# 10-Microcontroller-1.net
KiCad netlist of a schematic drawn in Altium Designer
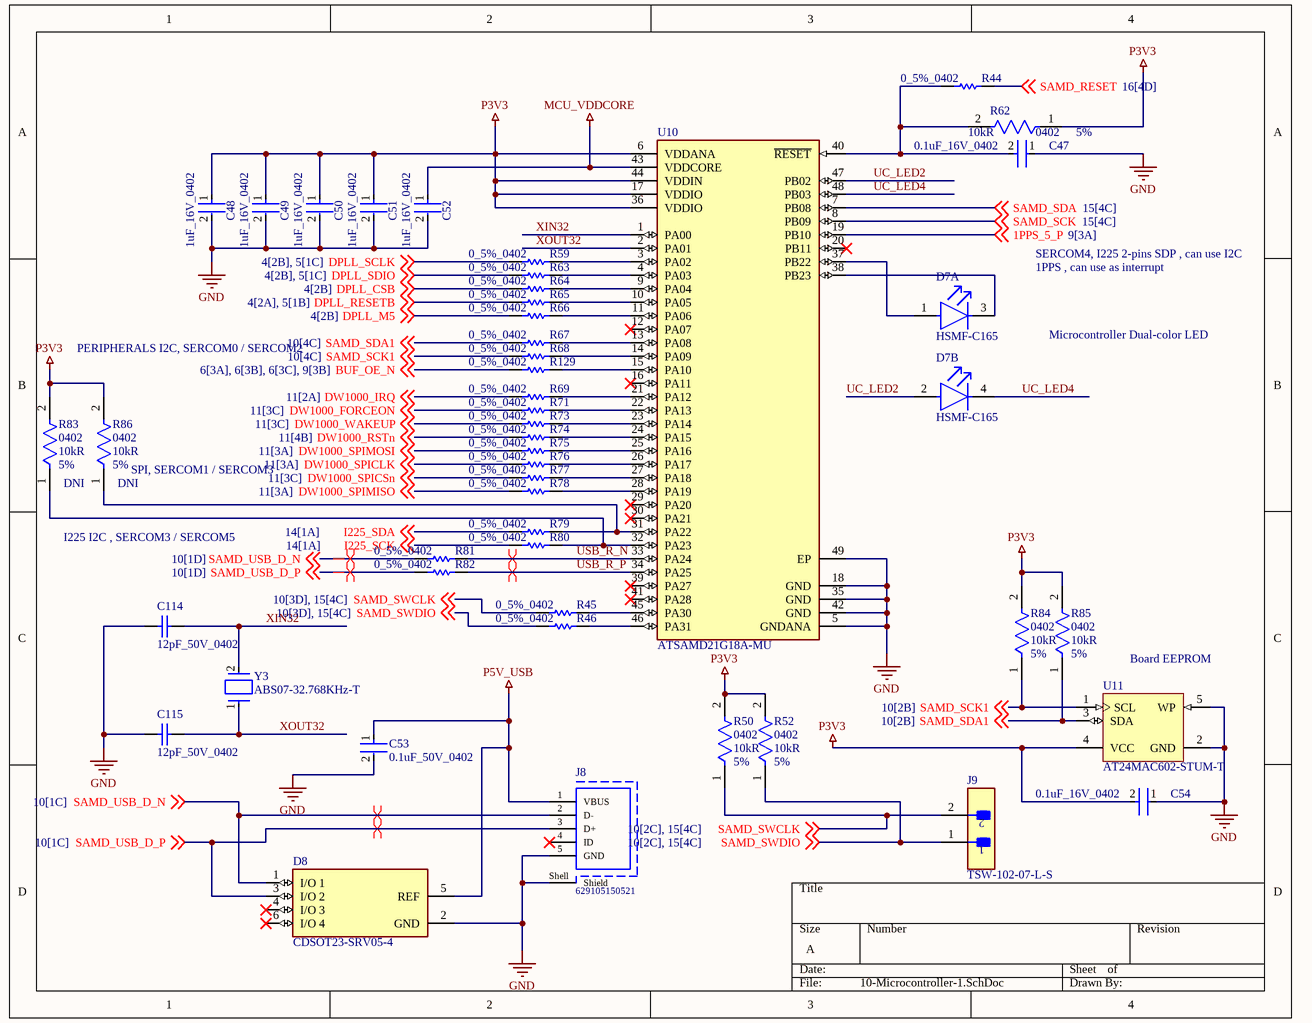
[diagram p0: 10-Microcontroller-1.SchDoc]

(export (version "E")
  (design (tool "Eeschema 10.0.6"))
  (components
    (comp (ref "C47")
      (value "0.1uF_16V_0402")
      (footprint "FP-GRM15-MFG")
      (description "CAP CER 0.1UF 16V X7R 0402")
      (fields (field (name "MANUFACTURER PART NUMBER") "GRM155R71C104KA88D") (field (name "TOLERANCE") "10%"))
      (libsource (lib "Altium Content Vault") (part "236180d848d6139a670b325ea6854c9"))
    )
    (comp (ref "C48")
      (value "1uF_16V_0402")
      (footprint "FP-0402-L_1_0_0_05-W_0_5-IPC_A")
      (description "None")
      (fields (field (name "TOLERANCE") "10%"))
      (libsource (lib "Altium Content Vault") (part "b4654b650e69147ec39a6b967a45e02"))
    )
    (comp (ref "C49")
      (value "1uF_16V_0402")
      (footprint "FP-0402-L_1_0_0_05-W_0_5-IPC_A")
      (description "None")
      (fields (field (name "TOLERANCE") "10%"))
      (libsource (lib "Altium Content Vault") (part "b4654b650e69147ec39a6b967a45e02"))
    )
    (comp (ref "C50")
      (value "1uF_16V_0402")
      (footprint "FP-0402-L_1_0_0_05-W_0_5-IPC_A")
      (description "None")
      (fields (field (name "TOLERANCE") "10%"))
      (libsource (lib "Altium Content Vault") (part "b4654b650e69147ec39a6b967a45e02"))
    )
    (comp (ref "C51")
      (value "1uF_16V_0402")
      (footprint "FP-0402-L_1_0_0_05-W_0_5-IPC_A")
      (description "None")
      (fields (field (name "TOLERANCE") "10%"))
      (libsource (lib "Altium Content Vault") (part "b4654b650e69147ec39a6b967a45e02"))
    )
    (comp (ref "C52")
      (value "1uF_16V_0402")
      (footprint "FP-0402-L_1_0_0_05-W_0_5-IPC_A")
      (description "None")
      (fields (field (name "TOLERANCE") "10%"))
      (libsource (lib "Altium Content Vault") (part "b4654b650e69147ec39a6b967a45e02"))
    )
    (comp (ref "C53")
      (value "0.1uF_50V_0402")
      (footprint "FP-C1005-050-0_05-IPC_C")
      (description "Multilayer Ceramic Capacitors 100nF ±10% 50V X7R SMD 0402")
      (fields (field (name "VOLTAGE") "50V") (field (name "TOLERANCE") "10%"))
      (libsource (lib "Altium Content Vault") (part "b4654b650e69147ec39a6b967a45e02"))
    )
    (comp (ref "C54")
      (value "0.1uF_16V_0402")
      (footprint "FP-GRM15-MFG")
      (description "CAP CER 0.1UF 16V X7R 0402")
      (fields (field (name "MANUFACTURER PART NUMBER") "GRM155R71C104KA88D") (field (name "TOLERANCE") "10%"))
      (libsource (lib "Altium Content Vault") (part "236180d848d6139a670b325ea6854c9"))
    )
    (comp (ref "C114")
      (value "12pF_50V_0402")
      (footprint "CAPC1005X55X25LL05T05")
      (description "Chip Capacitor, 12 pF, +/- 5%, 50 V, -55 to 125 degC, 0402 (1005 Metric), RoHS, Tape and Reel")
      (fields (field (name "MANUFACTURER") "Yageo") (field (name "TOLERANCE") "±5%"))
      (libsource (lib "Altium Content Vault") (part "CAP-NP-2"))
    )
    (comp (ref "C115")
      (value "12pF_50V_0402")
      (footprint "CAPC1005X55X25LL05T05")
      (description "Chip Capacitor, 12 pF, +/- 5%, 50 V, -55 to 125 degC, 0402 (1005 Metric), RoHS, Tape and Reel")
      (fields (field (name "MANUFACTURER") "Yageo") (field (name "TOLERANCE") "±5%"))
      (libsource (lib "Altium Content Vault") (part "CAP-NP-2"))
    )
    (comp (ref "D7")
      (value "HSMF-C165")
      (footprint "FP-HSMF-C165-MFG")
      (description "LED GREEN/RED DIFFUSED 0603 SMD")
      (libsource (lib "Altium Content Vault") (part "7c1fe340d8ce6b5db8c50b7ec3493de"))
    )
    (comp (ref "D8")
      (value "CDSOT23-SRV05-4")
      (footprint "FP-CDSOT23-SRV05-4-MFG")
      (description "TVS DIODE 5V 15V SOT23-6")
      (fields
        (field (name "OCTOPART") "https://octopart.com/cdsot23-srv05-4-bourns-1679449")
        (field (name "MANUFACTURER") "Bourns Inc.")
      )
      (libsource (lib "Altium Content Vault") (part "1f9d70c8dcd49be0b2fcd6c5f1da486"))
    )
    (comp (ref "J8")
      (value "629105150521")
      (footprint "629105150521")
      (description "Micro USB 2.0 Type B Receptacle WR-COM, Horizontal, SMT, with Pegs, High Current at Pin 1 & Pin 5")
      (fields (field (name "MANUFACTURER") "Wurth Elektronik") (field (name "PUBLISHER") "WurthElektronik"))
      (libsource (lib "Altium Content Vault") (part "WE-USB-5-1SHLD"))
    )
    (comp (ref "J9")
      (value "TSW-102-07-L-S")
      (footprint "FP-TSW-102-07-L-S-MFG")
      (description "CONN HEADER VERT 2POS 2.54MM")
      (libsource (lib "Altium Content Vault") (part "3bc925449376181038e59eaffc5286c"))
    )
    (comp (ref "R44")
      (value "0_5%_0402")
      (footprint "RESC1005X40X25LL10T10")
      (fields (field (name "MANUFACTURER") "KOA Speer") (field (name "PART NUMBER") "RK73Z1ETTP"))
      (libsource (lib "Altium Content Vault") (part "RES"))
    )
    (comp (ref "R45")
      (value "0_5%_0402")
      (footprint "RESC1005X40X25LL10T10")
      (fields (field (name "MANUFACTURER") "KOA Speer") (field (name "PART NUMBER") "RK73Z1ETTP"))
      (libsource (lib "Altium Content Vault") (part "RES"))
    )
    (comp (ref "R46")
      (value "0_5%_0402")
      (footprint "RESC1005X40X25LL10T10")
      (fields (field (name "MANUFACTURER") "KOA Speer") (field (name "PART NUMBER") "RK73Z1ETTP"))
      (libsource (lib "Altium Content Vault") (part "RES"))
    )
    (comp (ref "R50")
      (value "CRCW040210K0JNED")
      (footprint "FP-CRCW0402-e3-IPC_B")
      (description "RES Thick Film, 10kΩ, 5%, 0.063W, 200ppm/°C, 0402")
      (fields
        (field (name "CASE/PACKAGE") "0402")
        (field (name "RESISTANCE") "10kR")
        (field (name "TOLERANCE") "5%")
      )
      (libsource (lib "Altium Content Vault") (part "1029c3af85768c4190bb7ad29bc67b5"))
    )
    (comp (ref "R52")
      (value "CRCW040210K0JNED")
      (footprint "FP-CRCW0402-e3-IPC_B")
      (description "RES Thick Film, 10kΩ, 5%, 0.063W, 200ppm/°C, 0402")
      (fields
        (field (name "CASE/PACKAGE") "0402")
        (field (name "RESISTANCE") "10kR")
        (field (name "TOLERANCE") "5%")
      )
      (libsource (lib "Altium Content Vault") (part "1029c3af85768c4190bb7ad29bc67b5"))
    )
    (comp (ref "R59")
      (value "0_5%_0402")
      (footprint "RESC1005X40X25LL10T10")
      (fields (field (name "MANUFACTURER") "KOA Speer") (field (name "PART NUMBER") "RK73Z1ETTP"))
      (libsource (lib "Altium Content Vault") (part "RES"))
    )
    (comp (ref "R62")
      (value "CRCW040210K0JNED")
      (footprint "FP-CRCW0402-e3-IPC_B")
      (description "RES Thick Film, 10kΩ, 5%, 0.063W, 200ppm/°C, 0402")
      (fields
        (field (name "CASE/PACKAGE") "0402")
        (field (name "RESISTANCE") "10kR")
        (field (name "TOLERANCE") "5%")
      )
      (libsource (lib "Altium Content Vault") (part "1029c3af85768c4190bb7ad29bc67b5"))
    )
    (comp (ref "R63")
      (value "0_5%_0402")
      (footprint "RESC1005X40X25LL10T10")
      (fields (field (name "MANUFACTURER") "KOA Speer") (field (name "PART NUMBER") "RK73Z1ETTP"))
      (libsource (lib "Altium Content Vault") (part "RES"))
    )
    (comp (ref "R64")
      (value "0_5%_0402")
      (footprint "RESC1005X40X25LL10T10")
      (fields (field (name "MANUFACTURER") "KOA Speer") (field (name "PART NUMBER") "RK73Z1ETTP"))
      (libsource (lib "Altium Content Vault") (part "RES"))
    )
    (comp (ref "R65")
      (value "0_5%_0402")
      (footprint "RESC1005X40X25LL10T10")
      (fields (field (name "MANUFACTURER") "KOA Speer") (field (name "PART NUMBER") "RK73Z1ETTP"))
      (libsource (lib "Altium Content Vault") (part "RES"))
    )
    (comp (ref "R66")
      (value "0_5%_0402")
      (footprint "RESC1005X40X25LL10T10")
      (fields (field (name "MANUFACTURER") "KOA Speer") (field (name "PART NUMBER") "RK73Z1ETTP"))
      (libsource (lib "Altium Content Vault") (part "RES"))
    )
    (comp (ref "R67")
      (value "0_5%_0402")
      (footprint "RESC1005X40X25LL10T10")
      (fields (field (name "MANUFACTURER") "KOA Speer") (field (name "PART NUMBER") "RK73Z1ETTP"))
      (libsource (lib "Altium Content Vault") (part "RES"))
    )
    (comp (ref "R68")
      (value "0_5%_0402")
      (footprint "RESC1005X40X25LL10T10")
      (fields (field (name "MANUFACTURER") "KOA Speer") (field (name "PART NUMBER") "RK73Z1ETTP"))
      (libsource (lib "Altium Content Vault") (part "RES"))
    )
    (comp (ref "R69")
      (value "0_5%_0402")
      (footprint "RESC1005X40X25LL10T10")
      (fields (field (name "MANUFACTURER") "KOA Speer") (field (name "PART NUMBER") "RK73Z1ETTP"))
      (libsource (lib "Altium Content Vault") (part "RES"))
    )
    (comp (ref "R71")
      (value "0_5%_0402")
      (footprint "RESC1005X40X25LL10T10")
      (fields (field (name "MANUFACTURER") "KOA Speer") (field (name "PART NUMBER") "RK73Z1ETTP"))
      (libsource (lib "Altium Content Vault") (part "RES"))
    )
    (comp (ref "R73")
      (value "0_5%_0402")
      (footprint "RESC1005X40X25LL10T10")
      (fields (field (name "MANUFACTURER") "KOA Speer") (field (name "PART NUMBER") "RK73Z1ETTP"))
      (libsource (lib "Altium Content Vault") (part "RES"))
    )
    (comp (ref "R74")
      (value "0_5%_0402")
      (footprint "RESC1005X40X25LL10T10")
      (fields (field (name "MANUFACTURER") "KOA Speer") (field (name "PART NUMBER") "RK73Z1ETTP"))
      (libsource (lib "Altium Content Vault") (part "RES"))
    )
    (comp (ref "R75")
      (value "0_5%_0402")
      (footprint "RESC1005X40X25LL10T10")
      (fields (field (name "MANUFACTURER") "KOA Speer") (field (name "PART NUMBER") "RK73Z1ETTP"))
      (libsource (lib "Altium Content Vault") (part "RES"))
    )
    (comp (ref "R76")
      (value "0_5%_0402")
      (footprint "RESC1005X40X25LL10T10")
      (fields (field (name "MANUFACTURER") "KOA Speer") (field (name "PART NUMBER") "RK73Z1ETTP"))
      (libsource (lib "Altium Content Vault") (part "RES"))
    )
    (comp (ref "R77")
      (value "0_5%_0402")
      (footprint "RESC1005X40X25LL10T10")
      (fields (field (name "MANUFACTURER") "KOA Speer") (field (name "PART NUMBER") "RK73Z1ETTP"))
      (libsource (lib "Altium Content Vault") (part "RES"))
    )
    (comp (ref "R78")
      (value "0_5%_0402")
      (footprint "RESC1005X40X25LL10T10")
      (fields (field (name "MANUFACTURER") "KOA Speer") (field (name "PART NUMBER") "RK73Z1ETTP"))
      (libsource (lib "Altium Content Vault") (part "RES"))
    )
    (comp (ref "R79")
      (value "0_5%_0402")
      (footprint "RESC1005X40X25LL10T10")
      (fields (field (name "MANUFACTURER") "KOA Speer") (field (name "PART NUMBER") "RK73Z1ETTP"))
      (libsource (lib "Altium Content Vault") (part "RES"))
    )
    (comp (ref "R80")
      (value "0_5%_0402")
      (footprint "RESC1005X40X25LL10T10")
      (fields (field (name "MANUFACTURER") "KOA Speer") (field (name "PART NUMBER") "RK73Z1ETTP"))
      (libsource (lib "Altium Content Vault") (part "RES"))
    )
    (comp (ref "R81")
      (value "0_5%_0402")
      (footprint "RESC1005X40X25LL10T10")
      (fields (field (name "MANUFACTURER") "KOA Speer") (field (name "PART NUMBER") "RK73Z1ETTP"))
      (libsource (lib "Altium Content Vault") (part "RES"))
    )
    (comp (ref "R82")
      (value "0_5%_0402")
      (footprint "RESC1005X40X25LL10T10")
      (fields (field (name "MANUFACTURER") "KOA Speer") (field (name "PART NUMBER") "RK73Z1ETTP"))
      (libsource (lib "Altium Content Vault") (part "RES"))
    )
    (comp (ref "R83")
      (value "CRCW040210K0JNED")
      (footprint "FP-CRCW0402-e3-IPC_B")
      (description "RES Thick Film, 10kΩ, 5%, 0.063W, 200ppm/°C, 0402")
      (fields
        (field (name "CASE/PACKAGE") "0402")
        (field (name "RESISTANCE") "10kR")
        (field (name "TOLERANCE") "5%")
        (field (name "DNI") "DNI")
      )
      (libsource (lib "Altium Content Vault") (part "1029c3af85768c4190bb7ad29bc67b5"))
    )
    (comp (ref "R84")
      (value "CRCW040210K0JNED")
      (footprint "FP-CRCW0402-e3-IPC_B")
      (description "RES Thick Film, 10kΩ, 5%, 0.063W, 200ppm/°C, 0402")
      (fields
        (field (name "CASE/PACKAGE") "0402")
        (field (name "RESISTANCE") "10kR")
        (field (name "TOLERANCE") "5%")
      )
      (libsource (lib "Altium Content Vault") (part "1029c3af85768c4190bb7ad29bc67b5"))
    )
    (comp (ref "R85")
      (value "CRCW040210K0JNED")
      (footprint "FP-CRCW0402-e3-IPC_B")
      (description "RES Thick Film, 10kΩ, 5%, 0.063W, 200ppm/°C, 0402")
      (fields
        (field (name "CASE/PACKAGE") "0402")
        (field (name "RESISTANCE") "10kR")
        (field (name "TOLERANCE") "5%")
      )
      (libsource (lib "Altium Content Vault") (part "1029c3af85768c4190bb7ad29bc67b5"))
    )
    (comp (ref "R86")
      (value "CRCW040210K0JNED")
      (footprint "FP-CRCW0402-e3-IPC_B")
      (description "RES Thick Film, 10kΩ, 5%, 0.063W, 200ppm/°C, 0402")
      (fields
        (field (name "CASE/PACKAGE") "0402")
        (field (name "RESISTANCE") "10kR")
        (field (name "TOLERANCE") "5%")
        (field (name "DNI") "DNI")
      )
      (libsource (lib "Altium Content Vault") (part "1029c3af85768c4190bb7ad29bc67b5"))
    )
    (comp (ref "R129")
      (value "0_5%_0402")
      (footprint "RESC1005X40X25LL10T10")
      (fields (field (name "MANUFACTURER") "KOA Speer") (field (name "PART NUMBER") "RK73Z1ETTP"))
      (libsource (lib "Altium Content Vault") (part "RES"))
    )
    (comp (ref "U10")
      (value "ATSAMD21G18A-MU")
      (footprint "FP-C04-21493-MFG")
      (description "IC MCU 32BIT 256KB FLASH 48QFN")
      (libsource (lib "Altium Content Vault") (part "550eed7d4552ecbabbedec1abd3d356"))
    )
    (comp (ref "U11")
      (value "AT24MAC602-STUM-T")
      (footprint "ATML-5TS1_M")
      (fields (field (name "MANUFACTURER") "Atmel"))
      (libsource (lib "Altium Content Vault") (part "ATML-AT24CXXX-5TS1"))
    )
    (comp (ref "Y3")
      (value "ABS07-32.768KHz-T")
      (footprint "FP-ABS07-MFG")
      (description "CRYSTAL 32.7680KHZ 12.5PF SMD")
      (fields (field (name "TOLERANCE") "20ppm"))
      (libsource (lib "Altium Content Vault") (part "c23a69dc6c9e2f18f2079038eb95dd1"))
    )
  )
  (nets
    (net (code "1") (name "/UC_LED2") (class "Default")
      (node (ref "D7") (pin "2") (pinfunction "RED_A_2") (pintype "passive"))
      (node (ref "U10") (pin "47") (pinfunction "PB02_47") (pintype "bidirectional"))
    )
    (net (code "2") (name "/UC_LED4") (class "Default")
      (node (ref "D7") (pin "4") (pinfunction "RED_C_4") (pintype "passive"))
      (node (ref "U10") (pin "48") (pinfunction "PB03_48") (pintype "bidirectional"))
    )
    (net (code "3") (name "/USB_R_N") (class "Default")
      (node (ref "R81") (pin "2") (pinfunction "2_2") (pintype "passive"))
      (node (ref "U10") (pin "33") (pinfunction "PA24_33") (pintype "bidirectional"))
    )
    (net (code "4") (name "/USB_R_P") (class "Default")
      (node (ref "R82") (pin "2") (pinfunction "2_2") (pintype "passive"))
      (node (ref "U10") (pin "34") (pinfunction "PA25_34") (pintype "bidirectional"))
    )
    (net (code "5") (name "/XIN32") (class "Default")
      (node (ref "C114") (pin "1") (pinfunction "1_1") (pintype "passive"))
      (node (ref "U10") (pin "1") (pinfunction "PA00_1") (pintype "bidirectional"))
      (node (ref "Y3") (pin "2") (pinfunction "2_2") (pintype "passive"))
    )
    (net (code "6") (name "/XOUT32") (class "Default")
      (node (ref "C115") (pin "1") (pinfunction "1_1") (pintype "passive"))
      (node (ref "U10") (pin "2") (pinfunction "PA01_2") (pintype "bidirectional"))
      (node (ref "Y3") (pin "1") (pinfunction "1_1") (pintype "passive"))
    )
    (net (code "7") (name "1PPS_5_P") (class "Default")
      (node (ref "U10") (pin "19") (pinfunction "PB10_19") (pintype "bidirectional"))
    )
    (net (code "8") (name "BUF_OE_N") (class "Default")
      (node (ref "R129") (pin "1") (pinfunction "1_1") (pintype "passive"))
    )
    (net (code "9") (name "DPLL_CSB") (class "Default")
      (node (ref "R64") (pin "1") (pinfunction "1_1") (pintype "passive"))
    )
    (net (code "10") (name "DPLL_M5") (class "Default")
      (node (ref "R66") (pin "1") (pinfunction "1_1") (pintype "passive"))
    )
    (net (code "11") (name "DPLL_RESETB") (class "Default")
      (node (ref "R65") (pin "1") (pinfunction "1_1") (pintype "passive"))
    )
    (net (code "12") (name "DPLL_SCLK") (class "Default")
      (node (ref "R59") (pin "1") (pinfunction "1_1") (pintype "passive"))
    )
    (net (code "13") (name "DPLL_SDIO") (class "Default")
      (node (ref "R63") (pin "1") (pinfunction "1_1") (pintype "passive"))
    )
    (net (code "14") (name "DW1000_FORCEON") (class "Default")
      (node (ref "R71") (pin "1") (pinfunction "1_1") (pintype "passive"))
    )
    (net (code "15") (name "DW1000_IRQ") (class "Default")
      (node (ref "R69") (pin "1") (pinfunction "1_1") (pintype "passive"))
    )
    (net (code "16") (name "DW1000_RSTn") (class "Default")
      (node (ref "R74") (pin "1") (pinfunction "1_1") (pintype "passive"))
    )
    (net (code "17") (name "DW1000_SPICLK") (class "Default")
      (node (ref "R76") (pin "1") (pinfunction "1_1") (pintype "passive"))
    )
    (net (code "18") (name "DW1000_SPICSn") (class "Default")
      (node (ref "R77") (pin "1") (pinfunction "1_1") (pintype "passive"))
    )
    (net (code "19") (name "DW1000_SPIMISO") (class "Default")
      (node (ref "R78") (pin "1") (pinfunction "1_1") (pintype "passive"))
    )
    (net (code "20") (name "DW1000_SPIMOSI") (class "Default")
      (node (ref "R75") (pin "1") (pinfunction "1_1") (pintype "passive"))
    )
    (net (code "21") (name "DW1000_WAKEUP") (class "Default")
      (node (ref "R73") (pin "1") (pinfunction "1_1") (pintype "passive"))
    )
    (net (code "22") (name "GND") (class "Default")
      (node (ref "C114") (pin "2") (pinfunction "2_2") (pintype "passive"))
      (node (ref "C115") (pin "2") (pinfunction "2_2") (pintype "passive"))
      (node (ref "C47") (pin "1") (pinfunction "1_1") (pintype "passive"))
      (node (ref "C48") (pin "2") (pinfunction "2_2") (pintype "passive"))
      (node (ref "C49") (pin "2") (pinfunction "2_2") (pintype "passive"))
      (node (ref "C50") (pin "2") (pinfunction "2_2") (pintype "passive"))
      (node (ref "C51") (pin "2") (pinfunction "2_2") (pintype "passive"))
      (node (ref "C52") (pin "2") (pinfunction "2_2") (pintype "passive"))
      (node (ref "C53") (pin "2") (pinfunction "2_2") (pintype "passive"))
      (node (ref "C54") (pin "1") (pinfunction "1_1") (pintype "passive"))
      (node (ref "D8") (pin "2") (pinfunction "GND_2") (pintype "power_in"))
      (node (ref "J8") (pin "5") (pinfunction "GND_5") (pintype "passive"))
      (node (ref "J8") (pin "Shell") (pinfunction "Shield_Shell") (pintype "passive"))
      (node (ref "U10") (pin "18") (pinfunction "GND_18") (pintype "power_in"))
      (node (ref "U10") (pin "35") (pinfunction "GND_35") (pintype "power_in"))
      (node (ref "U10") (pin "42") (pinfunction "GND_42") (pintype "power_in"))
      (node (ref "U10") (pin "49") (pinfunction "EP_49") (pintype "power_in"))
      (node (ref "U10") (pin "5") (pinfunction "GNDANA_5") (pintype "power_in"))
      (node (ref "U11") (pin "2") (pinfunction "GND_2") (pintype "power_in"))
      (node (ref "U11") (pin "5") (pinfunction "WP_5") (pintype "input"))
    )
    (net (code "23") (name "I225_SCK") (class "Default")
      (node (ref "R80") (pin "1") (pinfunction "1_1") (pintype "passive"))
    )
    (net (code "24") (name "I225_SDA") (class "Default")
      (node (ref "R79") (pin "1") (pinfunction "1_1") (pintype "passive"))
    )
    (net (code "25") (name "MCU_VDDCORE") (class "Default")
      (node (ref "C52") (pin "1") (pinfunction "1_1") (pintype "passive"))
      (node (ref "U10") (pin "43") (pinfunction "VDDCORE_43") (pintype "power_in"))
    )
    (net (code "26") (name "Net-(D7A-GREEN_A)") (class "Default")
      (node (ref "D7") (pin "1") (pinfunction "GREEN_A_1") (pintype "passive"))
      (node (ref "U10") (pin "37") (pinfunction "PB22_37") (pintype "bidirectional"))
    )
    (net (code "27") (name "Net-(D7A-GREEN_C)") (class "Default")
      (node (ref "D7") (pin "3") (pinfunction "GREEN_C_3") (pintype "passive"))
      (node (ref "U10") (pin "38") (pinfunction "PB23_38") (pintype "bidirectional"))
    )
    (net (code "28") (name "Net-(U10-PA02)") (class "Default")
      (node (ref "R59") (pin "2") (pinfunction "2_2") (pintype "passive"))
      (node (ref "U10") (pin "3") (pinfunction "PA02_3") (pintype "bidirectional"))
    )
    (net (code "29") (name "Net-(U10-PA03)") (class "Default")
      (node (ref "R63") (pin "2") (pinfunction "2_2") (pintype "passive"))
      (node (ref "U10") (pin "4") (pinfunction "PA03_4") (pintype "bidirectional"))
    )
    (net (code "30") (name "Net-(U10-PA04)") (class "Default")
      (node (ref "R64") (pin "2") (pinfunction "2_2") (pintype "passive"))
      (node (ref "U10") (pin "9") (pinfunction "PA04_9") (pintype "bidirectional"))
    )
    (net (code "31") (name "Net-(U10-PA05)") (class "Default")
      (node (ref "R65") (pin "2") (pinfunction "2_2") (pintype "passive"))
      (node (ref "U10") (pin "10") (pinfunction "PA05_10") (pintype "bidirectional"))
    )
    (net (code "32") (name "Net-(U10-PA06)") (class "Default")
      (node (ref "R66") (pin "2") (pinfunction "2_2") (pintype "passive"))
      (node (ref "U10") (pin "11") (pinfunction "PA06_11") (pintype "bidirectional"))
    )
    (net (code "33") (name "Net-(U10-PA08)") (class "Default")
      (node (ref "R67") (pin "2") (pinfunction "2_2") (pintype "passive"))
      (node (ref "U10") (pin "13") (pinfunction "PA08_13") (pintype "bidirectional"))
    )
    (net (code "34") (name "Net-(U10-PA09)") (class "Default")
      (node (ref "R68") (pin "2") (pinfunction "2_2") (pintype "passive"))
      (node (ref "U10") (pin "14") (pinfunction "PA09_14") (pintype "bidirectional"))
    )
    (net (code "35") (name "Net-(U10-PA10)") (class "Default")
      (node (ref "R129") (pin "2") (pinfunction "2_2") (pintype "passive"))
      (node (ref "U10") (pin "15") (pinfunction "PA10_15") (pintype "bidirectional"))
    )
    (net (code "36") (name "Net-(U10-PA12)") (class "Default")
      (node (ref "R69") (pin "2") (pinfunction "2_2") (pintype "passive"))
      (node (ref "U10") (pin "21") (pinfunction "PA12_21") (pintype "bidirectional"))
    )
    (net (code "37") (name "Net-(U10-PA13)") (class "Default")
      (node (ref "R71") (pin "2") (pinfunction "2_2") (pintype "passive"))
      (node (ref "U10") (pin "22") (pinfunction "PA13_22") (pintype "bidirectional"))
    )
    (net (code "38") (name "Net-(U10-PA14)") (class "Default")
      (node (ref "R73") (pin "2") (pinfunction "2_2") (pintype "passive"))
      (node (ref "U10") (pin "23") (pinfunction "PA14_23") (pintype "bidirectional"))
    )
    (net (code "39") (name "Net-(U10-PA15)") (class "Default")
      (node (ref "R74") (pin "2") (pinfunction "2_2") (pintype "passive"))
      (node (ref "U10") (pin "24") (pinfunction "PA15_24") (pintype "bidirectional"))
    )
    (net (code "40") (name "Net-(U10-PA16)") (class "Default")
      (node (ref "R75") (pin "2") (pinfunction "2_2") (pintype "passive"))
      (node (ref "U10") (pin "25") (pinfunction "PA16_25") (pintype "bidirectional"))
    )
    (net (code "41") (name "Net-(U10-PA17)") (class "Default")
      (node (ref "R76") (pin "2") (pinfunction "2_2") (pintype "passive"))
      (node (ref "U10") (pin "26") (pinfunction "PA17_26") (pintype "bidirectional"))
    )
    (net (code "42") (name "Net-(U10-PA18)") (class "Default")
      (node (ref "R77") (pin "2") (pinfunction "2_2") (pintype "passive"))
      (node (ref "U10") (pin "27") (pinfunction "PA18_27") (pintype "bidirectional"))
    )
    (net (code "43") (name "Net-(U10-PA19)") (class "Default")
      (node (ref "R78") (pin "2") (pinfunction "2_2") (pintype "passive"))
      (node (ref "U10") (pin "28") (pinfunction "PA19_28") (pintype "bidirectional"))
    )
    (net (code "44") (name "Net-(U10-PA22)") (class "Default")
      (node (ref "R79") (pin "2") (pinfunction "2_2") (pintype "passive"))
      (node (ref "R86") (pin "1") (pinfunction "1_1") (pintype "passive"))
      (node (ref "U10") (pin "31") (pinfunction "PA22_31") (pintype "bidirectional"))
    )
    (net (code "45") (name "Net-(U10-PA23)") (class "Default")
      (node (ref "R80") (pin "2") (pinfunction "2_2") (pintype "passive"))
      (node (ref "R83") (pin "1") (pinfunction "1_1") (pintype "passive"))
      (node (ref "U10") (pin "32") (pinfunction "PA23_32") (pintype "bidirectional"))
    )
    (net (code "46") (name "Net-(U10-PA30)") (class "Default")
      (node (ref "R45") (pin "2") (pinfunction "2_2") (pintype "passive"))
      (node (ref "U10") (pin "45") (pinfunction "PA30_45") (pintype "bidirectional"))
    )
    (net (code "47") (name "Net-(U10-PA31)") (class "Default")
      (node (ref "R46") (pin "2") (pinfunction "2_2") (pintype "passive"))
      (node (ref "U10") (pin "46") (pinfunction "PA31_46") (pintype "bidirectional"))
    )
    (net (code "48") (name "Net-(U10-~{RESET})") (class "Default")
      (node (ref "C47") (pin "2") (pinfunction "2_2") (pintype "passive"))
      (node (ref "R44") (pin "1") (pinfunction "1_1") (pintype "passive"))
      (node (ref "R62") (pin "2") (pinfunction "2_2") (pintype "passive"))
      (node (ref "U10") (pin "40") (pinfunction "~{RESET}_40") (pintype "input"))
    )
    (net (code "49") (name "P3V3") (class "Default")
      (node (ref "C48") (pin "1") (pinfunction "1_1") (pintype "passive"))
      (node (ref "C49") (pin "1") (pinfunction "1_1") (pintype "passive"))
      (node (ref "C50") (pin "1") (pinfunction "1_1") (pintype "passive"))
      (node (ref "C51") (pin "1") (pinfunction "1_1") (pintype "passive"))
      (node (ref "C54") (pin "2") (pinfunction "2_2") (pintype "passive"))
      (node (ref "R50") (pin "2") (pinfunction "2_2") (pintype "passive"))
      (node (ref "R52") (pin "2") (pinfunction "2_2") (pintype "passive"))
      (node (ref "R62") (pin "1") (pinfunction "1_1") (pintype "passive"))
      (node (ref "R83") (pin "2") (pinfunction "2_2") (pintype "passive"))
      (node (ref "R84") (pin "2") (pinfunction "2_2") (pintype "passive"))
      (node (ref "R85") (pin "2") (pinfunction "2_2") (pintype "passive"))
      (node (ref "R86") (pin "2") (pinfunction "2_2") (pintype "passive"))
      (node (ref "U10") (pin "17") (pinfunction "VDDIO_17") (pintype "power_in"))
      (node (ref "U10") (pin "36") (pinfunction "VDDIO_36") (pintype "power_in"))
      (node (ref "U10") (pin "44") (pinfunction "VDDIN_44") (pintype "power_in"))
      (node (ref "U10") (pin "6") (pinfunction "VDDANA_6") (pintype "power_in"))
      (node (ref "U11") (pin "4") (pinfunction "VCC_4") (pintype "power_in"))
    )
    (net (code "50") (name "P5V_USB") (class "Default")
      (node (ref "C53") (pin "1") (pinfunction "1_1") (pintype "passive"))
      (node (ref "D8") (pin "5") (pinfunction "REF_5") (pintype "power_in"))
      (node (ref "J8") (pin "1") (pinfunction "VBUS_1") (pintype "passive"))
    )
    (net (code "51") (name "SAMD_RESET") (class "Default")
      (node (ref "R44") (pin "2") (pinfunction "2_2") (pintype "passive"))
    )
    (net (code "52") (name "SAMD_SCK") (class "Default")
      (node (ref "U10") (pin "8") (pinfunction "PB09_8") (pintype "bidirectional"))
    )
    (net (code "53") (name "SAMD_SCK1") (class "Default")
      (node (ref "R68") (pin "1") (pinfunction "1_1") (pintype "passive"))
      (node (ref "R84") (pin "1") (pinfunction "1_1") (pintype "passive"))
      (node (ref "U11") (pin "1") (pinfunction "SCL_1") (pintype "input"))
    )
    (net (code "54") (name "SAMD_SDA") (class "Default")
      (node (ref "U10") (pin "7") (pinfunction "PB08_7") (pintype "bidirectional"))
    )
    (net (code "55") (name "SAMD_SDA1") (class "Default")
      (node (ref "R67") (pin "1") (pinfunction "1_1") (pintype "passive"))
      (node (ref "R85") (pin "1") (pinfunction "1_1") (pintype "passive"))
      (node (ref "U11") (pin "3") (pinfunction "SDA_3") (pintype "bidirectional"))
    )
    (net (code "56") (name "SAMD_SWCLK") (class "Default")
      (node (ref "J9") (pin "2") (pinfunction "2_2") (pintype "passive"))
      (node (ref "R45") (pin "1") (pinfunction "1_1") (pintype "passive"))
      (node (ref "R50") (pin "1") (pinfunction "1_1") (pintype "passive"))
    )
    (net (code "57") (name "SAMD_SWDIO") (class "Default")
      (node (ref "J9") (pin "1") (pinfunction "1_1") (pintype "passive"))
      (node (ref "R46") (pin "1") (pinfunction "1_1") (pintype "passive"))
      (node (ref "R52") (pin "1") (pinfunction "1_1") (pintype "passive"))
    )
    (net (code "58") (name "SAMD_USB_D_N") (class "Default")
      (node (ref "D8") (pin "1") (pinfunction "I/O_1_1") (pintype "bidirectional"))
      (node (ref "J8") (pin "2") (pinfunction "D-_2") (pintype "passive"))
      (node (ref "R81") (pin "1") (pinfunction "1_1") (pintype "passive"))
    )
    (net (code "59") (name "SAMD_USB_D_P") (class "Default")
      (node (ref "D8") (pin "3") (pinfunction "I/O_2_3") (pintype "bidirectional"))
      (node (ref "J8") (pin "3") (pinfunction "D+_3") (pintype "passive"))
      (node (ref "R82") (pin "1") (pinfunction "1_1") (pintype "passive"))
    )
    (net (code "60") (name "unconnected-(D8-I{slash}O_3-Pad4)") (class "Default")
      (node (ref "D8") (pin "4") (pinfunction "I/O_3_4") (pintype "bidirectional+no_connect"))
    )
    (net (code "61") (name "unconnected-(D8-I{slash}O_4-Pad6)") (class "Default")
      (node (ref "D8") (pin "6") (pinfunction "I/O_4_6") (pintype "bidirectional+no_connect"))
    )
    (net (code "62") (name "unconnected-(J8-ID-Pad4)") (class "Default")
      (node (ref "J8") (pin "4") (pinfunction "ID_4") (pintype "passive+no_connect"))
    )
    (net (code "63") (name "unconnected-(U10-PA07-Pad12)") (class "Default")
      (node (ref "U10") (pin "12") (pinfunction "PA07_12") (pintype "bidirectional+no_connect"))
    )
    (net (code "64") (name "unconnected-(U10-PA11-Pad16)") (class "Default")
      (node (ref "U10") (pin "16") (pinfunction "PA11_16") (pintype "bidirectional+no_connect"))
    )
    (net (code "65") (name "unconnected-(U10-PA20-Pad29)") (class "Default")
      (node (ref "U10") (pin "29") (pinfunction "PA20_29") (pintype "bidirectional+no_connect"))
    )
    (net (code "66") (name "unconnected-(U10-PA21-Pad30)") (class "Default")
      (node (ref "U10") (pin "30") (pinfunction "PA21_30") (pintype "bidirectional+no_connect"))
    )
    (net (code "67") (name "unconnected-(U10-PA27-Pad39)") (class "Default")
      (node (ref "U10") (pin "39") (pinfunction "PA27_39") (pintype "bidirectional+no_connect"))
    )
    (net (code "68") (name "unconnected-(U10-PA28-Pad41)") (class "Default")
      (node (ref "U10") (pin "41") (pinfunction "PA28_41") (pintype "bidirectional+no_connect"))
    )
    (net (code "69") (name "unconnected-(U10-PB11-Pad20)") (class "Default")
      (node (ref "U10") (pin "20") (pinfunction "PB11_20") (pintype "bidirectional+no_connect"))
    )
  )
)
